# 36V_HV_Supply.net
KiCad netlist of a schematic drawn in Altium Designer
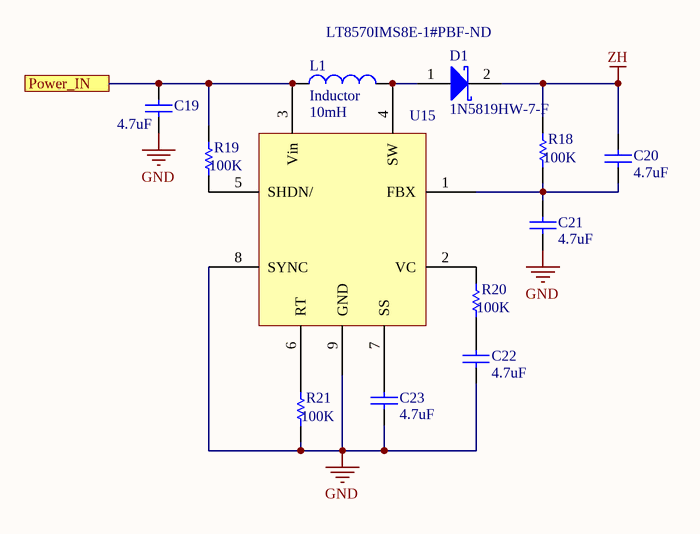
[diagram p0: 36V_HV_Supply.SchDoc]

(export (version "E")
  (design (tool "Eeschema 10.0.6"))
  (components
    (comp (ref "C19")
      (value "4.7uF")
      (footprint "CAPC1210(3225)100_M")
      (description "CAP CER 4.7UF 50V X7R 1210")
      (fields
        (field (name "MANUFACTURER") "Murata")
        (field (name "MANUFACTURER PART NUMBER") "GCM32ER71H475KA55K")
      )
      (libsource (lib "Altium Content Vault") (part "CAP"))
    )
    (comp (ref "C20")
      (value "4.7uF")
      (footprint "CAPC1210(3225)100_M")
      (description "CAP CER 4.7UF 50V X7R 1210")
      (fields
        (field (name "MANUFACTURER") "Murata")
        (field (name "MANUFACTURER PART NUMBER") "GCM32ER71H475KA55K")
      )
      (libsource (lib "Altium Content Vault") (part "CAP"))
    )
    (comp (ref "C21")
      (value "4.7uF")
      (footprint "CAPC1210(3225)100_M")
      (description "CAP CER 4.7UF 50V X7R 1210")
      (fields
        (field (name "MANUFACTURER") "Murata")
        (field (name "MANUFACTURER PART NUMBER") "GCM32ER71H475KA55K")
      )
      (libsource (lib "Altium Content Vault") (part "CAP"))
    )
    (comp (ref "C22")
      (value "4.7uF")
      (footprint "CAPC1210(3225)100_M")
      (description "CAP CER 4.7UF 50V X7R 1210")
      (fields
        (field (name "MANUFACTURER") "Murata")
        (field (name "MANUFACTURER PART NUMBER") "GCM32ER71H475KA55K")
      )
      (libsource (lib "Altium Content Vault") (part "CAP"))
    )
    (comp (ref "C23")
      (value "4.7uF")
      (footprint "CAPC1210(3225)100_M")
      (description "CAP CER 4.7UF 50V X7R 1210")
      (fields
        (field (name "MANUFACTURER") "Murata")
        (field (name "MANUFACTURER PART NUMBER") "GCM32ER71H475KA55K")
      )
      (libsource (lib "Altium Content Vault") (part "CAP"))
    )
    (comp (ref "D1")
      (value "1N5819HW-7-F")
      (footprint "DIOD-SOD-123-2_V")
      (fields (field (name "MANUFACTURER") "Diodes Inc"))
      (libsource (lib "Altium Content Vault") (part "DIOD-DSKY-A1K2-2"))
    )
    (comp (ref "L1")
      (value "Inductor")
      (footprint "0402-A")
      (fields (field (name "ALTIUM_VALUE") "10mH") (field (name "PUBLISHER") "Altium Limited"))
      (libsource (lib "Miscellaneous Devices") (part "Inductor"))
    )
    (comp (ref "R18")
      (value "RES SMD 100K OHM 1% 1/8W 0805")
      (footprint "RESC0805(2012)_M")
      (fields
        (field (name "MANUFACTURER") "Vishay")
        (field (name "MANUFACTURER PART NUMBER") "CRCW0805100KFKEA")
        (field (name "TOLERANCE") "1%")
        (field (name "RESISTANCE") "100K")
      )
      (libsource (lib "Altium Content Vault") (part "CMP-1013-00017-1"))
    )
    (comp (ref "R19")
      (value "RES SMD 100K OHM 1% 1/8W 0805")
      (footprint "RESC0805(2012)_M")
      (fields
        (field (name "MANUFACTURER") "Vishay")
        (field (name "MANUFACTURER PART NUMBER") "CRCW0805100KFKEA")
        (field (name "TOLERANCE") "1%")
        (field (name "RESISTANCE") "100K")
      )
      (libsource (lib "Altium Content Vault") (part "CMP-1013-00017-1"))
    )
    (comp (ref "R20")
      (value "RES SMD 100K OHM 1% 1/8W 0805")
      (footprint "RESC0805(2012)_M")
      (fields
        (field (name "MANUFACTURER") "Vishay")
        (field (name "MANUFACTURER PART NUMBER") "CRCW0805100KFKEA")
        (field (name "TOLERANCE") "1%")
        (field (name "RESISTANCE") "100K")
      )
      (libsource (lib "Altium Content Vault") (part "CMP-1013-00017-1"))
    )
    (comp (ref "R21")
      (value "RES SMD 100K OHM 1% 1/8W 0805")
      (footprint "RESC0805(2012)_M")
      (fields
        (field (name "MANUFACTURER") "Vishay")
        (field (name "MANUFACTURER PART NUMBER") "CRCW0805100KFKEA")
        (field (name "TOLERANCE") "1%")
        (field (name "RESISTANCE") "100K")
      )
      (libsource (lib "Altium Content Vault") (part "CMP-1013-00017-1"))
    )
    (comp (ref "U15")
      (value "LT8570")
      (footprint "LT8570-MSOP")
      (fields (field (name "SUPPLIER PART NUMBER 1") "LT8570IMS8E-1#PBF-ND"))
      (libsource (lib "ZLS_Schematic_lib") (part "LT8570"))
    )
  )
  (nets
    (net (code "1") (name "/Power_IN") (class "Default")
      (node (ref "C19") (pin "2") (pinfunction "2_2") (pintype "passive"))
      (node (ref "L1") (pin "1") (pinfunction "1_1") (pintype "passive"))
      (node (ref "R19") (pin "1") (pinfunction "1_1") (pintype "passive"))
      (node (ref "U15") (pin "3") (pinfunction "Vin_3") (pintype "passive"))
    )
    (net (code "2") (name "GND") (class "Default")
      (node (ref "C19") (pin "1") (pinfunction "1_1") (pintype "passive"))
      (node (ref "C21") (pin "1") (pinfunction "1_1") (pintype "passive"))
      (node (ref "C22") (pin "1") (pinfunction "1_1") (pintype "passive"))
      (node (ref "C23") (pin "1") (pinfunction "1_1") (pintype "passive"))
      (node (ref "R21") (pin "2") (pinfunction "2_2") (pintype "passive"))
      (node (ref "U15") (pin "8") (pinfunction "SYNC_8") (pintype "passive"))
      (node (ref "U15") (pin "9") (pinfunction "GND_9") (pintype "passive"))
    )
    (net (code "3") (name "Net-(C22-Pad2)") (class "Default")
      (node (ref "C22") (pin "2") (pinfunction "2_2") (pintype "passive"))
      (node (ref "R20") (pin "2") (pinfunction "2_2") (pintype "passive"))
    )
    (net (code "4") (name "Net-(D1-A)") (class "Default")
      (node (ref "D1") (pin "1") (pinfunction "A_1") (pintype "passive"))
      (node (ref "L1") (pin "2") (pinfunction "2_2") (pintype "passive"))
      (node (ref "U15") (pin "4") (pinfunction "SW_4") (pintype "passive"))
    )
    (net (code "5") (name "Net-(U15-FBX)") (class "Default")
      (node (ref "C20") (pin "1") (pinfunction "1_1") (pintype "passive"))
      (node (ref "C21") (pin "2") (pinfunction "2_2") (pintype "passive"))
      (node (ref "R18") (pin "2") (pinfunction "2_2") (pintype "passive"))
      (node (ref "U15") (pin "1") (pinfunction "FBX_1") (pintype "passive"))
    )
    (net (code "6") (name "Net-(U15-RT)") (class "Default")
      (node (ref "R21") (pin "1") (pinfunction "1_1") (pintype "passive"))
      (node (ref "U15") (pin "6") (pinfunction "RT_6") (pintype "passive"))
    )
    (net (code "7") (name "Net-(U15-SHDN{slash})") (class "Default")
      (node (ref "R19") (pin "2") (pinfunction "2_2") (pintype "passive"))
      (node (ref "U15") (pin "5") (pinfunction "SHDN/_5") (pintype "passive"))
    )
    (net (code "8") (name "Net-(U15-SS)") (class "Default")
      (node (ref "C23") (pin "2") (pinfunction "2_2") (pintype "passive"))
      (node (ref "U15") (pin "7") (pinfunction "SS_7") (pintype "passive"))
    )
    (net (code "9") (name "Net-(U15-VC)") (class "Default")
      (node (ref "R20") (pin "1") (pinfunction "1_1") (pintype "passive"))
      (node (ref "U15") (pin "2") (pinfunction "VC_2") (pintype "passive"))
    )
    (net (code "10") (name "ZH") (class "Default")
      (node (ref "C20") (pin "2") (pinfunction "2_2") (pintype "passive"))
      (node (ref "D1") (pin "2") (pinfunction "K_2") (pintype "passive"))
      (node (ref "R18") (pin "1") (pinfunction "1_1") (pintype "passive"))
    )
  )
)
